# Metal_Detctor_V1.net
KiCad netlist of a schematic drawn in EAGLE
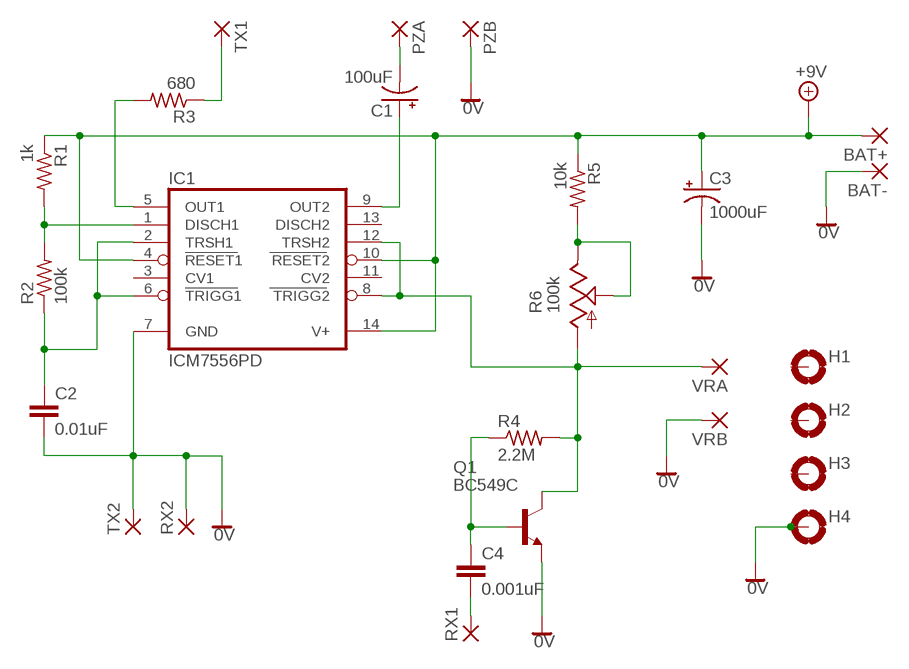
[diagram p0: schematic, sheet 1]

(export (version "E")
  (design (tool "Eeschema 10.0.6"))
  (components
    (comp (ref "BAT+")
      (value "WIREPAD2,54/1,1")
      (footprint "eagle-import:2,54_1,1")
      (libsource (lib "eagle-import") (part "WIREPAD2,54/1,1"))
    )
    (comp (ref "BAT-")
      (value "WIREPAD2,54/1,1")
      (footprint "eagle-import:2,54_1,1")
      (libsource (lib "eagle-import") (part "WIREPAD2,54/1,1"))
    )
    (comp (ref "C1")
      (value "100uF")
      (footprint "eagle-import:E5-8,5")
      (libsource (lib "eagle-import") (part "CPOL-USE5-8.5"))
    )
    (comp (ref "C2")
      (value "0.01uF")
      (footprint "eagle-import:C050-024X044")
      (libsource (lib "eagle-import") (part "C-EU050-024X044"))
    )
    (comp (ref "C3")
      (value "1000uF")
      (footprint "eagle-import:E5-10,5")
      (libsource (lib "eagle-import") (part "CPOL-USE5-10.5"))
    )
    (comp (ref "C4")
      (value "0.001uF")
      (footprint "eagle-import:C050-024X044")
      (libsource (lib "eagle-import") (part "C-EU050-024X044"))
    )
    (comp (ref "H1")
      (value "MOUNT-PAD-ROUND3.0")
      (footprint "eagle-import:3,0-PAD")
      (libsource (lib "eagle-import") (part "MOUNT-PAD-ROUND3.0"))
    )
    (comp (ref "H2")
      (value "MOUNT-PAD-ROUND3.0")
      (footprint "eagle-import:3,0-PAD")
      (libsource (lib "eagle-import") (part "MOUNT-PAD-ROUND3.0"))
    )
    (comp (ref "H3")
      (value "MOUNT-PAD-ROUND3.0")
      (footprint "eagle-import:3,0-PAD")
      (libsource (lib "eagle-import") (part "MOUNT-PAD-ROUND3.0"))
    )
    (comp (ref "H4")
      (value "MOUNT-PAD-ROUND3.0")
      (footprint "eagle-import:3,0-PAD")
      (libsource (lib "eagle-import") (part "MOUNT-PAD-ROUND3.0"))
    )
    (comp (ref "IC1")
      (value "ICM7556PD")
      (footprint "eagle-import:DIL14")
      (libsource (lib "eagle-import") (part "ICM7556PD"))
    )
    (comp (ref "PZA")
      (value "WIREPAD2,54/1,1")
      (footprint "eagle-import:2,54_1,1")
      (libsource (lib "eagle-import") (part "WIREPAD2,54/1,1"))
    )
    (comp (ref "PZB")
      (value "WIREPAD2,54/1,1")
      (footprint "eagle-import:2,54_1,1")
      (libsource (lib "eagle-import") (part "WIREPAD2,54/1,1"))
    )
    (comp (ref "Q1")
      (value "BC549C")
      (footprint "eagle-import:TO92-EBC")
      (libsource (lib "eagle-import") (part "BC549C"))
    )
    (comp (ref "R1")
      (value "1k")
      (footprint "eagle-import:0207_12")
      (libsource (lib "eagle-import") (part "R-US_0207/12"))
    )
    (comp (ref "R2")
      (value "100k")
      (footprint "eagle-import:0207_12")
      (libsource (lib "eagle-import") (part "R-US_0207/12"))
    )
    (comp (ref "R3")
      (value "680")
      (footprint "eagle-import:0207_12")
      (libsource (lib "eagle-import") (part "R-US_0207/12"))
    )
    (comp (ref "R4")
      (value "2.2M")
      (footprint "eagle-import:0207_12")
      (libsource (lib "eagle-import") (part "R-US_0207/12"))
    )
    (comp (ref "R5")
      (value "10k")
      (footprint "eagle-import:0207_12")
      (libsource (lib "eagle-import") (part "R-US_0207/12"))
    )
    (comp (ref "R6")
      (value "100k")
      (footprint "eagle-import:SP19L")
      (libsource (lib "eagle-import") (part "TRIM_US-B90P"))
    )
    (comp (ref "RX1")
      (value "WIREPAD2,54/1,1")
      (footprint "eagle-import:2,54_1,1")
      (libsource (lib "eagle-import") (part "WIREPAD2,54/1,1"))
    )
    (comp (ref "RX2")
      (value "WIREPAD2,54/1,1")
      (footprint "eagle-import:2,54_1,1")
      (libsource (lib "eagle-import") (part "WIREPAD2,54/1,1"))
    )
    (comp (ref "TX1")
      (value "WIREPAD2,54/1,1")
      (footprint "eagle-import:2,54_1,1")
      (libsource (lib "eagle-import") (part "WIREPAD2,54/1,1"))
    )
    (comp (ref "TX2")
      (value "WIREPAD2,54/1,1")
      (footprint "eagle-import:2,54_1,1")
      (libsource (lib "eagle-import") (part "WIREPAD2,54/1,1"))
    )
    (comp (ref "VRA")
      (value "WIREPAD2,54/1,1")
      (footprint "eagle-import:2,54_1,1")
      (libsource (lib "eagle-import") (part "WIREPAD2,54/1,1"))
    )
    (comp (ref "VRB")
      (value "WIREPAD2,54/1,1")
      (footprint "eagle-import:2,54_1,1")
      (libsource (lib "eagle-import") (part "WIREPAD2,54/1,1"))
    )
  )
  (nets
    (net (code "1") (name "+9V") (class "Default")
      (node (ref "BAT+") (pin "1") (pinfunction "P_1") (pintype "passive"))
      (node (ref "C3") (pin "+") (pinfunction "+_+") (pintype "passive"))
      (node (ref "IC1") (pin "10") (pinfunction "RESET2_10") (pintype "input"))
      (node (ref "IC1") (pin "14") (pinfunction "V+_14") (pintype "power_in"))
      (node (ref "IC1") (pin "4") (pinfunction "RESET1_4") (pintype "input"))
      (node (ref "R1") (pin "1") (pinfunction "1_1") (pintype "passive"))
      (node (ref "R5") (pin "1") (pinfunction "1_1") (pintype "passive"))
    )
    (net (code "2") (name "0V") (class "Default")
      (node (ref "BAT-") (pin "1") (pinfunction "P_1") (pintype "passive"))
      (node (ref "C2") (pin "2") (pinfunction "2_2") (pintype "passive"))
      (node (ref "C3") (pin "-") (pinfunction "-_-") (pintype "passive"))
      (node (ref "H4") (pin "B3,0") (pinfunction "MOUNT_B3,0") (pintype "passive"))
      (node (ref "IC1") (pin "7") (pinfunction "GND_7") (pintype "power_in"))
      (node (ref "PZB") (pin "1") (pinfunction "P_1") (pintype "passive"))
      (node (ref "Q1") (pin "E") (pinfunction "E_E") (pintype "passive"))
      (node (ref "RX2") (pin "1") (pinfunction "P_1") (pintype "passive"))
      (node (ref "TX2") (pin "1") (pinfunction "P_1") (pintype "passive"))
      (node (ref "VRB") (pin "1") (pinfunction "P_1") (pintype "passive"))
    )
    (net (code "3") (name "Net-(C4-Pad1)") (class "Default")
      (node (ref "C4") (pin "1") (pinfunction "1_1") (pintype "passive"))
      (node (ref "Q1") (pin "B") (pinfunction "B_B") (pintype "passive"))
      (node (ref "R4") (pin "1") (pinfunction "1_1") (pintype "passive"))
    )
    (net (code "4") (name "Net-(IC1-DISCH1)") (class "Default")
      (node (ref "IC1") (pin "1") (pinfunction "DISCH1_1") (pintype "input"))
      (node (ref "R1") (pin "2") (pinfunction "2_2") (pintype "passive"))
      (node (ref "R2") (pin "2") (pinfunction "2_2") (pintype "passive"))
    )
    (net (code "5") (name "Net-(IC1-OUT1)") (class "Default")
      (node (ref "IC1") (pin "5") (pinfunction "OUT1_5") (pintype "output"))
      (node (ref "R3") (pin "2") (pinfunction "2_2") (pintype "passive"))
    )
    (net (code "6") (name "Net-(IC1-OUT2)") (class "Default")
      (node (ref "C1") (pin "+") (pinfunction "+_+") (pintype "passive"))
      (node (ref "IC1") (pin "9") (pinfunction "OUT2_9") (pintype "output"))
    )
    (net (code "7") (name "Net-(IC1-TRIGG1)") (class "Default")
      (node (ref "C2") (pin "1") (pinfunction "1_1") (pintype "passive"))
      (node (ref "IC1") (pin "2") (pinfunction "TRSH1_2") (pintype "input"))
      (node (ref "IC1") (pin "6") (pinfunction "TRIGG1_6") (pintype "bidirectional"))
      (node (ref "R2") (pin "1") (pinfunction "1_1") (pintype "passive"))
    )
    (net (code "8") (name "Net-(IC1-TRIGG2)") (class "Default")
      (node (ref "IC1") (pin "12") (pinfunction "TRSH2_12") (pintype "input"))
      (node (ref "IC1") (pin "8") (pinfunction "TRIGG2_8") (pintype "bidirectional"))
      (node (ref "Q1") (pin "C") (pinfunction "C_C") (pintype "passive"))
      (node (ref "R4") (pin "2") (pinfunction "2_2") (pintype "passive"))
      (node (ref "R6") (pin "A") (pinfunction "A_A") (pintype "passive"))
      (node (ref "VRA") (pin "1") (pinfunction "P_1") (pintype "passive"))
    )
    (net (code "9") (name "Net-(PZA-P)") (class "Default")
      (node (ref "C1") (pin "-") (pinfunction "-_-") (pintype "passive"))
      (node (ref "PZA") (pin "1") (pinfunction "P_1") (pintype "passive"))
    )
    (net (code "10") (name "Net-(R5-Pad2)") (class "Default")
      (node (ref "R5") (pin "2") (pinfunction "2_2") (pintype "passive"))
      (node (ref "R6") (pin "E") (pinfunction "E_E") (pintype "passive"))
      (node (ref "R6") (pin "S") (pinfunction "S_S") (pintype "passive"))
    )
    (net (code "11") (name "Net-(RX1-P)") (class "Default")
      (node (ref "C4") (pin "2") (pinfunction "2_2") (pintype "passive"))
      (node (ref "RX1") (pin "1") (pinfunction "P_1") (pintype "passive"))
    )
    (net (code "12") (name "Net-(TX1-P)") (class "Default")
      (node (ref "R3") (pin "1") (pinfunction "1_1") (pintype "passive"))
      (node (ref "TX1") (pin "1") (pinfunction "P_1") (pintype "passive"))
    )
    (net (code "13") (name "unconnected-(H1-MOUNT-PadB3,0)") (class "Default")
      (node (ref "H1") (pin "B3,0") (pinfunction "MOUNT_B3,0") (pintype "passive"))
    )
    (net (code "14") (name "unconnected-(H2-MOUNT-PadB3,0)") (class "Default")
      (node (ref "H2") (pin "B3,0") (pinfunction "MOUNT_B3,0") (pintype "passive"))
    )
    (net (code "15") (name "unconnected-(H3-MOUNT-PadB3,0)") (class "Default")
      (node (ref "H3") (pin "B3,0") (pinfunction "MOUNT_B3,0") (pintype "passive"))
    )
    (net (code "16") (name "unconnected-(IC1-CV1-Pad3)") (class "Default")
      (node (ref "IC1") (pin "3") (pinfunction "CV1_3") (pintype "passive"))
    )
    (net (code "17") (name "unconnected-(IC1-CV2-Pad11)") (class "Default")
      (node (ref "IC1") (pin "11") (pinfunction "CV2_11") (pintype "passive"))
    )
    (net (code "18") (name "unconnected-(IC1-DISCH2-Pad13)") (class "Default")
      (node (ref "IC1") (pin "13") (pinfunction "DISCH2_13") (pintype "input"))
    )
  )
)
